# MSSRP-TC_IF.net
KiCad netlist of a schematic drawn in EAGLE
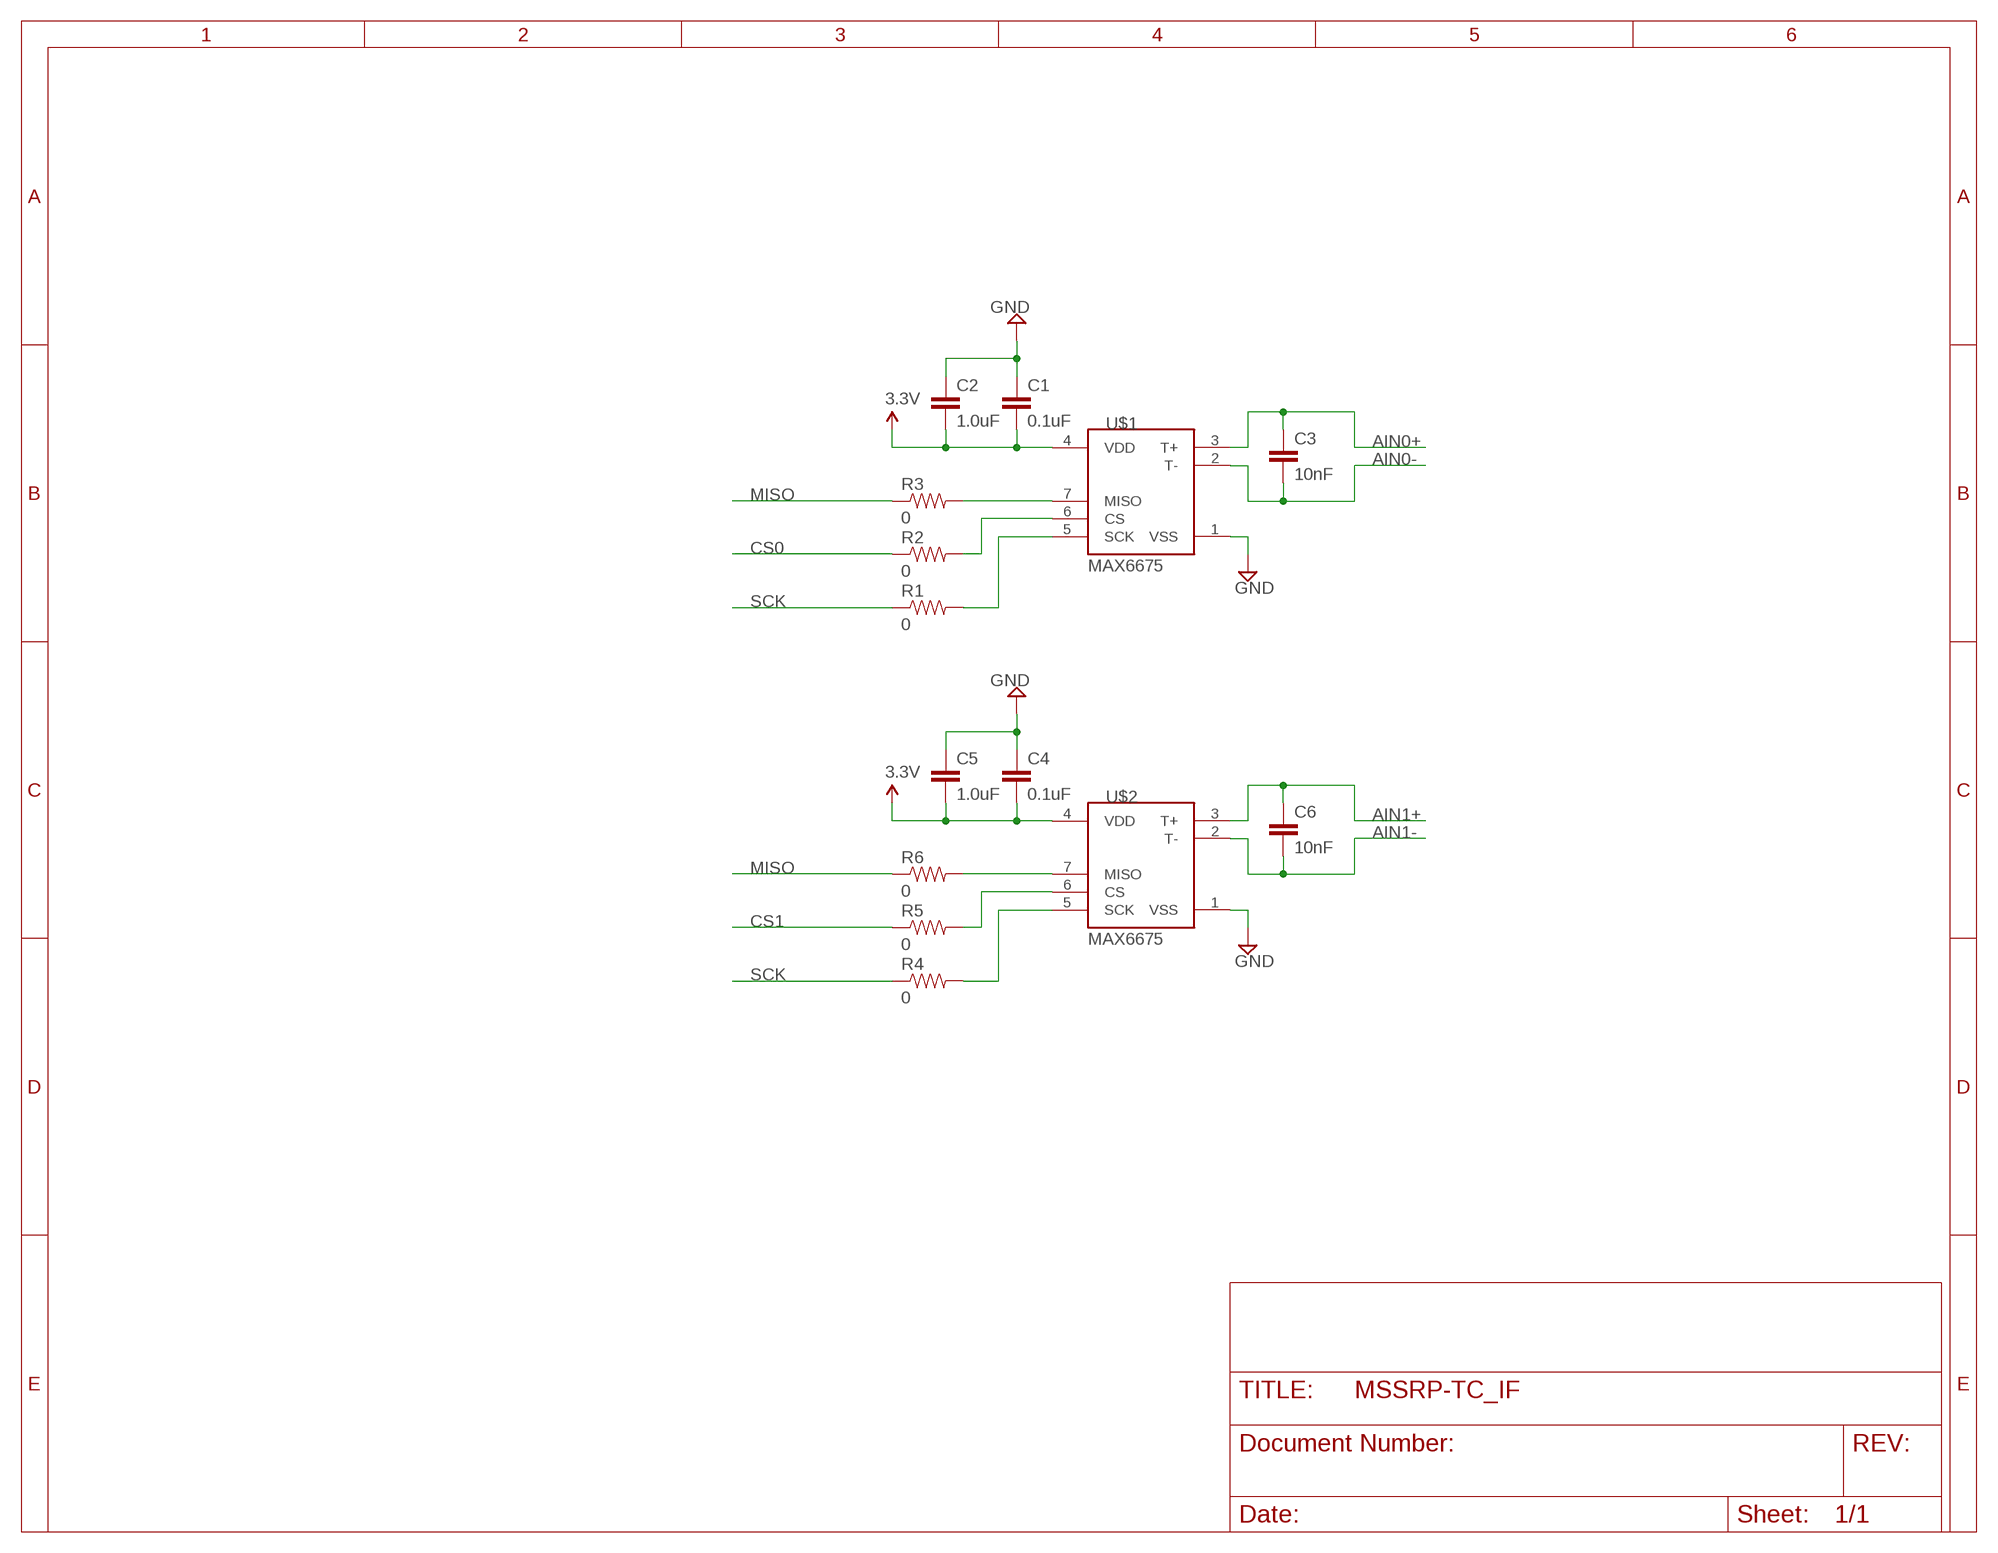
[diagram p0: schematic, sheet 1]

(export (version "E")
  (design (tool "Eeschema 10.0.6"))
  (components
    (comp (ref "C1")
      (value "0.1uF")
      (footprint "eagle-import:0603-CAP")
      (libsource (lib "eagle-import") (part "0.1UF-25V-5%(0603)"))
    )
    (comp (ref "C2")
      (value "1.0uF")
      (footprint "eagle-import:0603-CAP")
      (libsource (lib "eagle-import") (part "1.0UF-16V-10%(0603)"))
    )
    (comp (ref "C3")
      (value "10nF")
      (footprint "eagle-import:0603-CAP")
      (libsource (lib "eagle-import") (part "10NF/10000PF-50V-10%(0603)"))
    )
    (comp (ref "C4")
      (value "0.1uF")
      (footprint "eagle-import:0603-CAP")
      (libsource (lib "eagle-import") (part "0.1UF-25V-5%(0603)"))
    )
    (comp (ref "C5")
      (value "1.0uF")
      (footprint "eagle-import:0603-CAP")
      (libsource (lib "eagle-import") (part "1.0UF-16V-10%(0603)"))
    )
    (comp (ref "C6")
      (value "10nF")
      (footprint "eagle-import:0603-CAP")
      (libsource (lib "eagle-import") (part "10NF/10000PF-50V-10%(0603)"))
    )
    (comp (ref "R1")
      (value "0")
      (footprint "eagle-import:0603")
      (libsource (lib "eagle-import") (part "0OHM1/10W5%(0603)"))
    )
    (comp (ref "R2")
      (value "0")
      (footprint "eagle-import:0603")
      (libsource (lib "eagle-import") (part "0OHM1/10W5%(0603)"))
    )
    (comp (ref "R3")
      (value "0")
      (footprint "eagle-import:0603")
      (libsource (lib "eagle-import") (part "0OHM1/10W5%(0603)"))
    )
    (comp (ref "R4")
      (value "0")
      (footprint "eagle-import:0603")
      (libsource (lib "eagle-import") (part "0OHM1/10W5%(0603)"))
    )
    (comp (ref "R5")
      (value "0")
      (footprint "eagle-import:0603")
      (libsource (lib "eagle-import") (part "0OHM1/10W5%(0603)"))
    )
    (comp (ref "R6")
      (value "0")
      (footprint "eagle-import:0603")
      (libsource (lib "eagle-import") (part "0OHM1/10W5%(0603)"))
    )
    (comp (ref "U$1")
      (value "MAX6675")
      (footprint "eagle-import:SO08-MAX6675")
      (libsource (lib "eagle-import") (part "MAX6675"))
    )
    (comp (ref "U$2")
      (value "MAX6675")
      (footprint "eagle-import:SO08-MAX6675")
      (libsource (lib "eagle-import") (part "MAX6675"))
    )
  )
  (nets
    (net (code "1") (name "/AIN0+") (class "Default")
      (node (ref "C3") (pin "1") (pinfunction "1_1") (pintype "passive"))
      (node (ref "U$1") (pin "3") (pinfunction "T+_3") (pintype "bidirectional"))
    )
    (net (code "2") (name "/AIN0-") (class "Default")
      (node (ref "C3") (pin "2") (pinfunction "2_2") (pintype "passive"))
      (node (ref "U$1") (pin "2") (pinfunction "T-_2") (pintype "bidirectional"))
    )
    (net (code "3") (name "/AIN1+") (class "Default")
      (node (ref "C6") (pin "1") (pinfunction "1_1") (pintype "passive"))
      (node (ref "U$2") (pin "3") (pinfunction "T+_3") (pintype "bidirectional"))
    )
    (net (code "4") (name "/AIN1-") (class "Default")
      (node (ref "C6") (pin "2") (pinfunction "2_2") (pintype "passive"))
      (node (ref "U$2") (pin "2") (pinfunction "T-_2") (pintype "bidirectional"))
    )
    (net (code "5") (name "/CS0") (class "Default")
      (node (ref "R2") (pin "1") (pinfunction "1_1") (pintype "passive"))
    )
    (net (code "6") (name "/CS1") (class "Default")
      (node (ref "R5") (pin "1") (pinfunction "1_1") (pintype "passive"))
    )
    (net (code "7") (name "/MISO") (class "Default")
      (node (ref "R3") (pin "1") (pinfunction "1_1") (pintype "passive"))
      (node (ref "R6") (pin "1") (pinfunction "1_1") (pintype "passive"))
    )
    (net (code "8") (name "/SCK") (class "Default")
      (node (ref "R1") (pin "1") (pinfunction "1_1") (pintype "passive"))
      (node (ref "R4") (pin "1") (pinfunction "1_1") (pintype "passive"))
    )
    (net (code "9") (name "3.3V") (class "Default")
      (node (ref "C1") (pin "2") (pinfunction "2_2") (pintype "passive"))
      (node (ref "C2") (pin "2") (pinfunction "2_2") (pintype "passive"))
      (node (ref "C4") (pin "2") (pinfunction "2_2") (pintype "passive"))
      (node (ref "C5") (pin "2") (pinfunction "2_2") (pintype "passive"))
      (node (ref "U$1") (pin "4") (pinfunction "VDD_4") (pintype "bidirectional"))
      (node (ref "U$2") (pin "4") (pinfunction "VDD_4") (pintype "bidirectional"))
    )
    (net (code "10") (name "GND") (class "Default")
      (node (ref "C1") (pin "1") (pinfunction "1_1") (pintype "passive"))
      (node (ref "C2") (pin "1") (pinfunction "1_1") (pintype "passive"))
      (node (ref "C4") (pin "1") (pinfunction "1_1") (pintype "passive"))
      (node (ref "C5") (pin "1") (pinfunction "1_1") (pintype "passive"))
      (node (ref "U$1") (pin "1") (pinfunction "VSS_1") (pintype "bidirectional"))
      (node (ref "U$2") (pin "1") (pinfunction "VSS_1") (pintype "bidirectional"))
    )
    (net (code "11") (name "Net-(U$1-CS)") (class "Default")
      (node (ref "R2") (pin "2") (pinfunction "2_2") (pintype "passive"))
      (node (ref "U$1") (pin "6") (pinfunction "CS_6") (pintype "bidirectional"))
    )
    (net (code "12") (name "Net-(U$1-MISO)") (class "Default")
      (node (ref "R3") (pin "2") (pinfunction "2_2") (pintype "passive"))
      (node (ref "U$1") (pin "7") (pinfunction "MISO_7") (pintype "bidirectional"))
    )
    (net (code "13") (name "Net-(U$1-SCK)") (class "Default")
      (node (ref "R1") (pin "2") (pinfunction "2_2") (pintype "passive"))
      (node (ref "U$1") (pin "5") (pinfunction "SCK_5") (pintype "bidirectional"))
    )
    (net (code "14") (name "Net-(U$2-CS)") (class "Default")
      (node (ref "R5") (pin "2") (pinfunction "2_2") (pintype "passive"))
      (node (ref "U$2") (pin "6") (pinfunction "CS_6") (pintype "bidirectional"))
    )
    (net (code "15") (name "Net-(U$2-MISO)") (class "Default")
      (node (ref "R6") (pin "2") (pinfunction "2_2") (pintype "passive"))
      (node (ref "U$2") (pin "7") (pinfunction "MISO_7") (pintype "bidirectional"))
    )
    (net (code "16") (name "Net-(U$2-SCK)") (class "Default")
      (node (ref "R4") (pin "2") (pinfunction "2_2") (pintype "passive"))
      (node (ref "U$2") (pin "5") (pinfunction "SCK_5") (pintype "bidirectional"))
    )
  )
)
